# CS_EPS.net
KiCad netlist of a schematic drawn in EAGLE
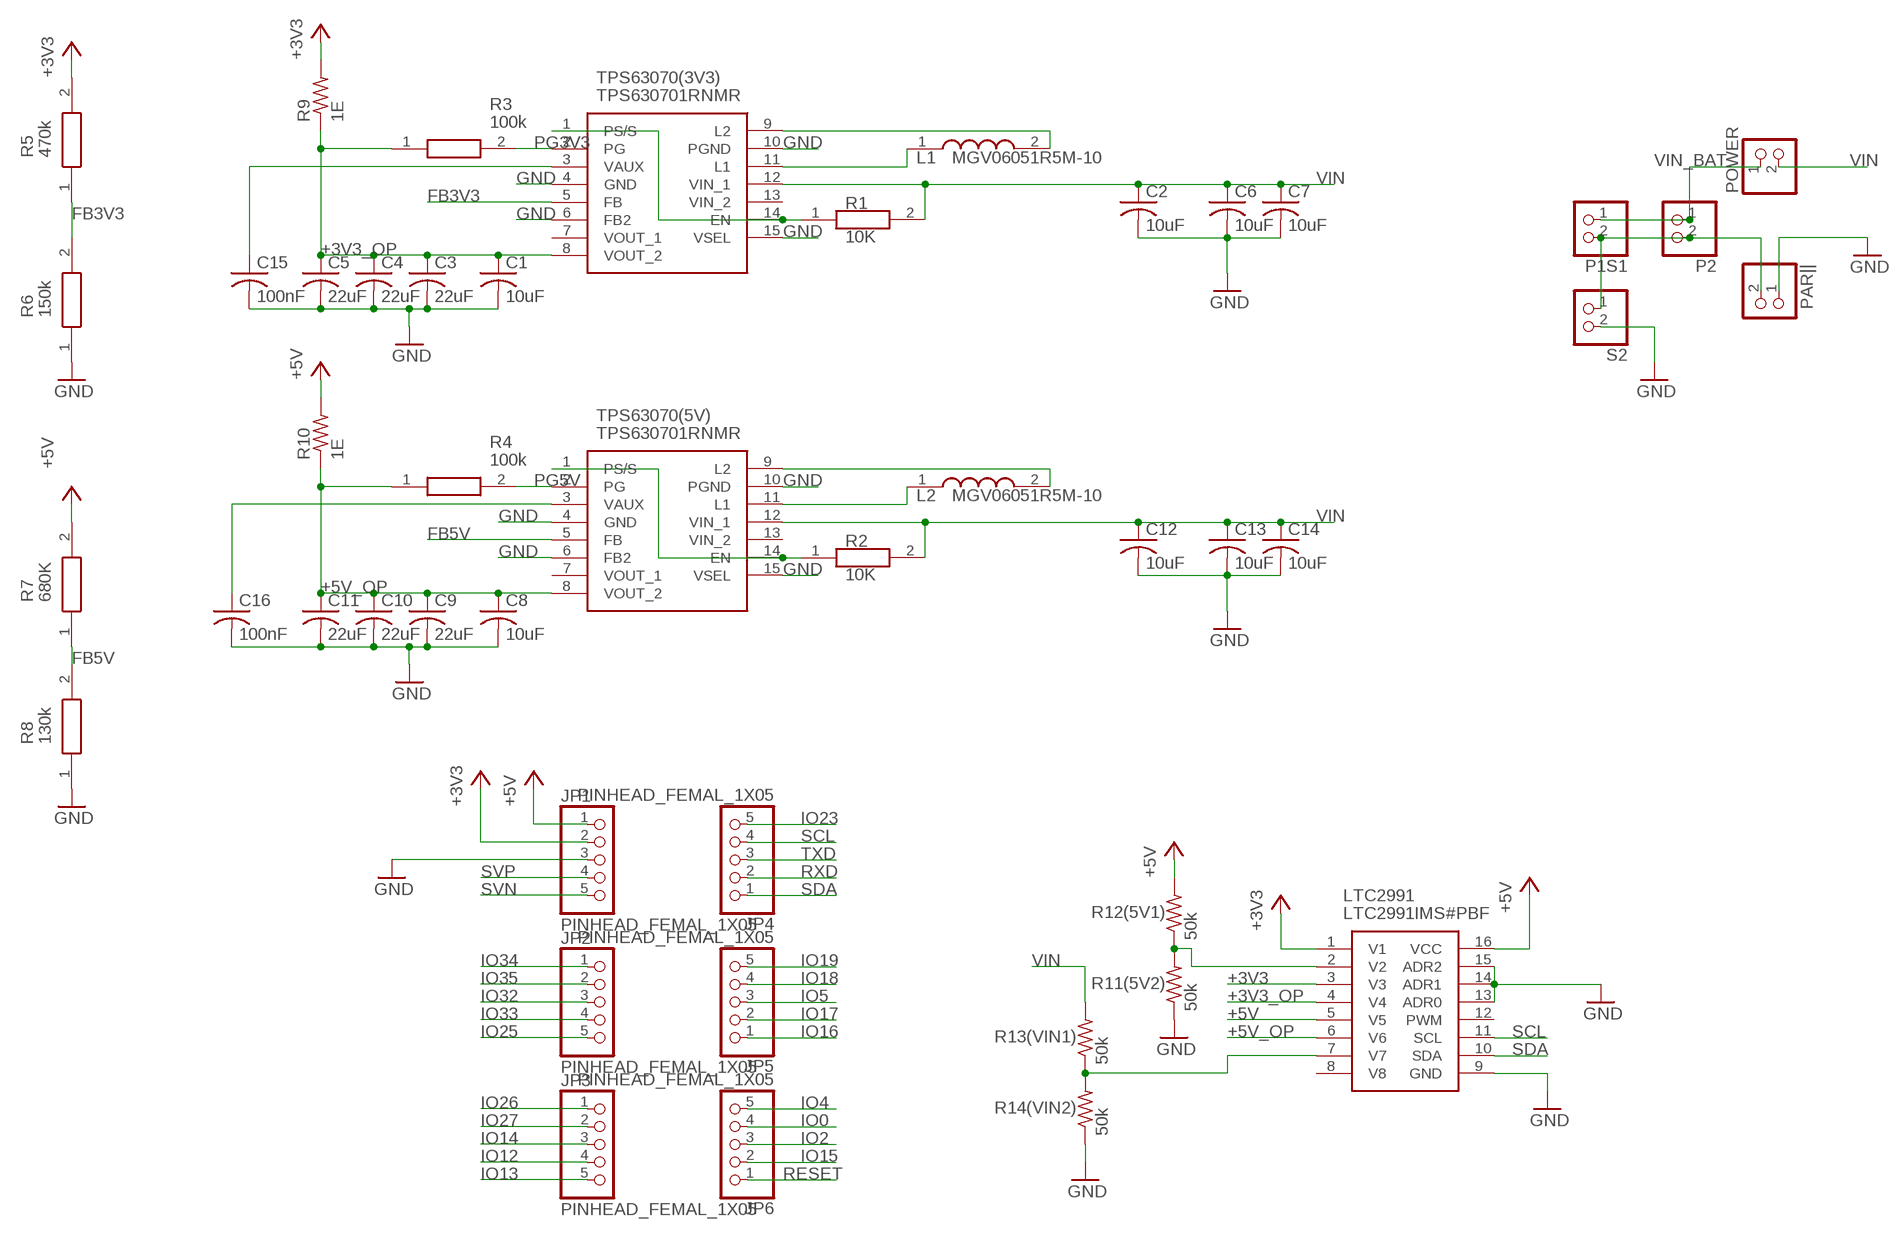
[diagram p0: schematic, sheet 1]

(export (version "E")
  (design (tool "Eeschema 10.0.6"))
  (components
    (comp (ref "C1")
      (value "10uF")
      (footprint "eagle-import:C0603K")
      (libsource (lib "eagle-import") (part "C-USC0603K"))
    )
    (comp (ref "C2")
      (value "10uF")
      (footprint "eagle-import:C0603K")
      (libsource (lib "eagle-import") (part "C-USC0603K"))
    )
    (comp (ref "C3")
      (value "22uF")
      (footprint "eagle-import:C0805K")
      (libsource (lib "eagle-import") (part "C-USC0805K"))
    )
    (comp (ref "C4")
      (value "22uF")
      (footprint "eagle-import:C0805K")
      (libsource (lib "eagle-import") (part "C-USC0805K"))
    )
    (comp (ref "C5")
      (value "22uF")
      (footprint "eagle-import:C0805K")
      (libsource (lib "eagle-import") (part "C-USC0805K"))
    )
    (comp (ref "C6")
      (value "10uF")
      (footprint "eagle-import:C0805K")
      (libsource (lib "eagle-import") (part "C-USC0805K"))
    )
    (comp (ref "C7")
      (value "10uF")
      (footprint "eagle-import:C0805K")
      (libsource (lib "eagle-import") (part "C-USC0805K"))
    )
    (comp (ref "C8")
      (value "10uF")
      (footprint "eagle-import:C0603K")
      (libsource (lib "eagle-import") (part "C-USC0603K"))
    )
    (comp (ref "C9")
      (value "22uF")
      (footprint "eagle-import:C0805K")
      (libsource (lib "eagle-import") (part "C-USC0805K"))
    )
    (comp (ref "C10")
      (value "22uF")
      (footprint "eagle-import:C0805K")
      (libsource (lib "eagle-import") (part "C-USC0805K"))
    )
    (comp (ref "C11")
      (value "22uF")
      (footprint "eagle-import:C0805K")
      (libsource (lib "eagle-import") (part "C-USC0805K"))
    )
    (comp (ref "C12")
      (value "10uF")
      (footprint "eagle-import:C0603K")
      (libsource (lib "eagle-import") (part "C-USC0603K"))
    )
    (comp (ref "C13")
      (value "10uF")
      (footprint "eagle-import:C0805K")
      (libsource (lib "eagle-import") (part "C-USC0805K"))
    )
    (comp (ref "C14")
      (value "10uF")
      (footprint "eagle-import:C0805K")
      (libsource (lib "eagle-import") (part "C-USC0805K"))
    )
    (comp (ref "C15")
      (value "100nF")
      (footprint "eagle-import:C0402")
      (libsource (lib "eagle-import") (part "C-USC0402"))
    )
    (comp (ref "C16")
      (value "100nF")
      (footprint "eagle-import:C0402")
      (libsource (lib "eagle-import") (part "C-USC0402"))
    )
    (comp (ref "JP1")
      (value "PINHEAD_FEMAL_1X05")
      (footprint "eagle-import:1X05F")
      (libsource (lib "eagle-import") (part "PINHEAD_FEMAL_1X05"))
    )
    (comp (ref "JP2")
      (value "PINHEAD_FEMAL_1X05")
      (footprint "eagle-import:1X05F")
      (libsource (lib "eagle-import") (part "PINHEAD_FEMAL_1X05"))
    )
    (comp (ref "JP3")
      (value "PINHEAD_FEMAL_1X05")
      (footprint "eagle-import:1X05F")
      (libsource (lib "eagle-import") (part "PINHEAD_FEMAL_1X05"))
    )
    (comp (ref "JP4")
      (value "PINHEAD_FEMAL_1X05")
      (footprint "eagle-import:1X05F")
      (libsource (lib "eagle-import") (part "PINHEAD_FEMAL_1X05"))
    )
    (comp (ref "JP5")
      (value "PINHEAD_FEMAL_1X05")
      (footprint "eagle-import:1X05F")
      (libsource (lib "eagle-import") (part "PINHEAD_FEMAL_1X05"))
    )
    (comp (ref "JP6")
      (value "PINHEAD_FEMAL_1X05")
      (footprint "eagle-import:1X05F")
      (libsource (lib "eagle-import") (part "PINHEAD_FEMAL_1X05"))
    )
    (comp (ref "L1")
      (value "MGV06051R5M-10")
      (footprint "eagle-import:INDPM7367X530N")
      (fields (field (name "MOUSER_PART_NUMBER") "875-MGV06051R5M-10"))
      (libsource (lib "eagle-import") (part "MGV06051R5M-10"))
    )
    (comp (ref "L2")
      (value "MGV06051R5M-10")
      (footprint "eagle-import:INDPM7367X530N")
      (fields (field (name "MOUSER_PART_NUMBER") "875-MGV06051R5M-10"))
      (libsource (lib "eagle-import") (part "MGV06051R5M-10"))
    )
    (comp (ref "LTC2991")
      (value "LTC2991IMS#PBF")
      (footprint "eagle-import:SOP50P490X110-16N")
      (fields (field (name "MOUSER_PART_NUMBER") "584-LTC2991IMS#PBF"))
      (libsource (lib "eagle-import") (part "LTC2991IMS#PBF"))
    )
    (comp (ref "P1S1")
      (value "JST_2PIN-THM")
      (footprint "eagle-import:JST-PH-2-THM")
      (libsource (lib "eagle-import") (part "JST_2PIN-THM"))
    )
    (comp (ref "P2")
      (value "JST_2PIN-THM")
      (footprint "eagle-import:JST-PH-2-THM")
      (libsource (lib "eagle-import") (part "JST_2PIN-THM"))
    )
    (comp (ref "PAR||")
      (value "PINHD-1X2")
      (footprint "eagle-import:1X02")
      (libsource (lib "eagle-import") (part "PINHD-1X2"))
    )
    (comp (ref "POWER")
      (value "PINHD-1X2")
      (footprint "eagle-import:1X02")
      (libsource (lib "eagle-import") (part "PINHD-1X2"))
    )
    (comp (ref "R1")
      (value "10K")
      (footprint "eagle-import:RESC2012X60N")
      (fields
        (field (name "MANUFACTURER_PART_NUMBER") "ERA-6AED134V")
        (field (name "MOUSER_PART_NUMBER") "667-ERA-6AED134V")
      )
      (libsource (lib "eagle-import") (part "ERA-6AED134V"))
    )
    (comp (ref "R2")
      (value "10K")
      (footprint "eagle-import:RESC2012X60N")
      (fields
        (field (name "MANUFACTURER_PART_NUMBER") "ERA-6AED134V")
        (field (name "MOUSER_PART_NUMBER") "667-ERA-6AED134V")
      )
      (libsource (lib "eagle-import") (part "ERA-6AED134V"))
    )
    (comp (ref "R3")
      (value "100k")
      (footprint "eagle-import:RESC2012X60N")
      (fields
        (field (name "MANUFACTURER_PART_NUMBER") "ERA-6AED134V")
        (field (name "MOUSER_PART_NUMBER") "667-ERA-6AED134V")
      )
      (libsource (lib "eagle-import") (part "ERA-6AED134V"))
    )
    (comp (ref "R4")
      (value "100k")
      (footprint "eagle-import:RESC2012X60N")
      (fields
        (field (name "MANUFACTURER_PART_NUMBER") "ERA-6AED134V")
        (field (name "MOUSER_PART_NUMBER") "667-ERA-6AED134V")
      )
      (libsource (lib "eagle-import") (part "ERA-6AED134V"))
    )
    (comp (ref "R5")
      (value "470k")
      (footprint "eagle-import:RESC2012X60N")
      (fields
        (field (name "MANUFACTURER_PART_NUMBER") "ERA-6AED134V")
        (field (name "MOUSER_PART_NUMBER") "667-ERA-6AED134V")
      )
      (libsource (lib "eagle-import") (part "ERA-6AED134V"))
    )
    (comp (ref "R6")
      (value "150k")
      (footprint "eagle-import:RESC2012X60N")
      (fields
        (field (name "MANUFACTURER_PART_NUMBER") "ERA-6AED134V")
        (field (name "MOUSER_PART_NUMBER") "667-ERA-6AED134V")
      )
      (libsource (lib "eagle-import") (part "ERA-6AED134V"))
    )
    (comp (ref "R7")
      (value "680K")
      (footprint "eagle-import:RESC2012X60N")
      (fields
        (field (name "MANUFACTURER_PART_NUMBER") "ERA-6AED134V")
        (field (name "MOUSER_PART_NUMBER") "667-ERA-6AED134V")
      )
      (libsource (lib "eagle-import") (part "ERA-6AED134V"))
    )
    (comp (ref "R8")
      (value "130k")
      (footprint "eagle-import:RESC2012X60N")
      (fields
        (field (name "MANUFACTURER_PART_NUMBER") "ERA-6AED134V")
        (field (name "MOUSER_PART_NUMBER") "667-ERA-6AED134V")
      )
      (libsource (lib "eagle-import") (part "ERA-6AED134V"))
    )
    (comp (ref "R9")
      (value "1E")
      (footprint "eagle-import:R0805")
      (libsource (lib "eagle-import") (part "R-US_R0805"))
    )
    (comp (ref "R10")
      (value "1E")
      (footprint "eagle-import:R0805")
      (libsource (lib "eagle-import") (part "R-US_R0805"))
    )
    (comp (ref "R11(5V2)")
      (value "50k")
      (footprint "eagle-import:R0805")
      (libsource (lib "eagle-import") (part "R-US_R0805"))
    )
    (comp (ref "R12(5V1)")
      (value "50k")
      (footprint "eagle-import:R0805")
      (libsource (lib "eagle-import") (part "R-US_R0805"))
    )
    (comp (ref "R13(VIN1)")
      (value "50k")
      (footprint "eagle-import:R0805")
      (libsource (lib "eagle-import") (part "R-US_R0805"))
    )
    (comp (ref "R14(VIN2)")
      (value "50k")
      (footprint "eagle-import:R0805")
      (libsource (lib "eagle-import") (part "R-US_R0805"))
    )
    (comp (ref "S2")
      (value "JST_2PIN-THM")
      (footprint "eagle-import:JST-PH-2-THM")
      (libsource (lib "eagle-import") (part "JST_2PIN-THM"))
    )
    (comp (ref "TPS63070(3V3)")
      (value "TPS630701RNMR")
      (footprint "eagle-import:TPS630701RNMR")
      (fields (field (name "MOUSER_PART_NUMBER") "595-TPS630701RNMR"))
      (libsource (lib "eagle-import") (part "TPS630701RNMR"))
    )
    (comp (ref "TPS63070(5V)")
      (value "TPS630701RNMR")
      (footprint "eagle-import:TPS630701RNMR")
      (fields (field (name "MOUSER_PART_NUMBER") "595-TPS630701RNMR"))
      (libsource (lib "eagle-import") (part "TPS630701RNMR"))
    )
  )
  (nets
    (net (code "1") (name "+3V3") (class "Default")
      (node (ref "JP1") (pin "2") (pinfunction "2_2") (pintype "passive"))
      (node (ref "LTC2991") (pin "1") (pinfunction "V1_1") (pintype "bidirectional"))
      (node (ref "LTC2991") (pin "3") (pinfunction "V3_3") (pintype "bidirectional"))
      (node (ref "R5") (pin "2") (pinfunction "2_2") (pintype "bidirectional"))
      (node (ref "R9") (pin "2") (pinfunction "2_2") (pintype "passive"))
    )
    (net (code "2") (name "+5V") (class "Default")
      (node (ref "JP1") (pin "1") (pinfunction "1_1") (pintype "passive"))
      (node (ref "LTC2991") (pin "16") (pinfunction "VCC_16") (pintype "bidirectional"))
      (node (ref "LTC2991") (pin "5") (pinfunction "V5_5") (pintype "bidirectional"))
      (node (ref "R10") (pin "2") (pinfunction "2_2") (pintype "passive"))
      (node (ref "R12(5V1)") (pin "2") (pinfunction "2_2") (pintype "passive"))
      (node (ref "R7") (pin "2") (pinfunction "2_2") (pintype "bidirectional"))
    )
    (net (code "3") (name "/+3V3_OP") (class "Default")
      (node (ref "C1") (pin "1") (pinfunction "1_1") (pintype "passive"))
      (node (ref "C3") (pin "1") (pinfunction "1_1") (pintype "passive"))
      (node (ref "C4") (pin "1") (pinfunction "1_1") (pintype "passive"))
      (node (ref "C5") (pin "1") (pinfunction "1_1") (pintype "passive"))
      (node (ref "LTC2991") (pin "4") (pinfunction "V4_4") (pintype "bidirectional"))
      (node (ref "R3") (pin "1") (pinfunction "1_1") (pintype "bidirectional"))
      (node (ref "R9") (pin "1") (pinfunction "1_1") (pintype "passive"))
      (node (ref "TPS63070(3V3)") (pin "8") (pinfunction "VOUT_2_8") (pintype "bidirectional"))
    )
    (net (code "4") (name "/+5V_OP") (class "Default")
      (node (ref "C10") (pin "1") (pinfunction "1_1") (pintype "passive"))
      (node (ref "C11") (pin "1") (pinfunction "1_1") (pintype "passive"))
      (node (ref "C8") (pin "1") (pinfunction "1_1") (pintype "passive"))
      (node (ref "C9") (pin "1") (pinfunction "1_1") (pintype "passive"))
      (node (ref "LTC2991") (pin "6") (pinfunction "V6_6") (pintype "bidirectional"))
      (node (ref "R10") (pin "1") (pinfunction "1_1") (pintype "passive"))
      (node (ref "R4") (pin "1") (pinfunction "1_1") (pintype "bidirectional"))
      (node (ref "TPS63070(5V)") (pin "8") (pinfunction "VOUT_2_8") (pintype "bidirectional"))
    )
    (net (code "5") (name "/FB3V3") (class "Default")
      (node (ref "R5") (pin "1") (pinfunction "1_1") (pintype "bidirectional"))
      (node (ref "R6") (pin "2") (pinfunction "2_2") (pintype "bidirectional"))
      (node (ref "TPS63070(3V3)") (pin "5") (pinfunction "FB_5") (pintype "bidirectional"))
    )
    (net (code "6") (name "/FB5V") (class "Default")
      (node (ref "R7") (pin "1") (pinfunction "1_1") (pintype "bidirectional"))
      (node (ref "R8") (pin "2") (pinfunction "2_2") (pintype "bidirectional"))
      (node (ref "TPS63070(5V)") (pin "5") (pinfunction "FB_5") (pintype "bidirectional"))
    )
    (net (code "7") (name "/IO0") (class "Default")
      (node (ref "JP6") (pin "4") (pinfunction "4_4") (pintype "passive"))
    )
    (net (code "8") (name "/IO2") (class "Default")
      (node (ref "JP6") (pin "3") (pinfunction "3_3") (pintype "passive"))
    )
    (net (code "9") (name "/IO4") (class "Default")
      (node (ref "JP6") (pin "5") (pinfunction "5_5") (pintype "passive"))
    )
    (net (code "10") (name "/IO5") (class "Default")
      (node (ref "JP5") (pin "3") (pinfunction "3_3") (pintype "passive"))
    )
    (net (code "11") (name "/IO12") (class "Default")
      (node (ref "JP3") (pin "4") (pinfunction "4_4") (pintype "passive"))
    )
    (net (code "12") (name "/IO13") (class "Default")
      (node (ref "JP3") (pin "5") (pinfunction "5_5") (pintype "passive"))
    )
    (net (code "13") (name "/IO14") (class "Default")
      (node (ref "JP3") (pin "3") (pinfunction "3_3") (pintype "passive"))
    )
    (net (code "14") (name "/IO15") (class "Default")
      (node (ref "JP6") (pin "2") (pinfunction "2_2") (pintype "passive"))
    )
    (net (code "15") (name "/IO16") (class "Default")
      (node (ref "JP5") (pin "1") (pinfunction "1_1") (pintype "passive"))
    )
    (net (code "16") (name "/IO17") (class "Default")
      (node (ref "JP5") (pin "2") (pinfunction "2_2") (pintype "passive"))
    )
    (net (code "17") (name "/IO18") (class "Default")
      (node (ref "JP5") (pin "4") (pinfunction "4_4") (pintype "passive"))
    )
    (net (code "18") (name "/IO19") (class "Default")
      (node (ref "JP5") (pin "5") (pinfunction "5_5") (pintype "passive"))
    )
    (net (code "19") (name "/IO23") (class "Default")
      (node (ref "JP4") (pin "5") (pinfunction "5_5") (pintype "passive"))
    )
    (net (code "20") (name "/IO25") (class "Default")
      (node (ref "JP2") (pin "5") (pinfunction "5_5") (pintype "passive"))
    )
    (net (code "21") (name "/IO26") (class "Default")
      (node (ref "JP3") (pin "1") (pinfunction "1_1") (pintype "passive"))
    )
    (net (code "22") (name "/IO27") (class "Default")
      (node (ref "JP3") (pin "2") (pinfunction "2_2") (pintype "passive"))
    )
    (net (code "23") (name "/IO32") (class "Default")
      (node (ref "JP2") (pin "3") (pinfunction "3_3") (pintype "passive"))
    )
    (net (code "24") (name "/IO33") (class "Default")
      (node (ref "JP2") (pin "4") (pinfunction "4_4") (pintype "passive"))
    )
    (net (code "25") (name "/IO34") (class "Default")
      (node (ref "JP2") (pin "1") (pinfunction "1_1") (pintype "passive"))
    )
    (net (code "26") (name "/IO35") (class "Default")
      (node (ref "JP2") (pin "2") (pinfunction "2_2") (pintype "passive"))
    )
    (net (code "27") (name "/PG3V3") (class "Default")
      (node (ref "R3") (pin "2") (pinfunction "2_2") (pintype "bidirectional"))
      (node (ref "TPS63070(3V3)") (pin "2") (pinfunction "PG_2") (pintype "bidirectional"))
    )
    (net (code "28") (name "/PG5V") (class "Default")
      (node (ref "R4") (pin "2") (pinfunction "2_2") (pintype "bidirectional"))
      (node (ref "TPS63070(5V)") (pin "2") (pinfunction "PG_2") (pintype "bidirectional"))
    )
    (net (code "29") (name "/RESET") (class "Default")
      (node (ref "JP6") (pin "1") (pinfunction "1_1") (pintype "passive"))
    )
    (net (code "30") (name "/RXD") (class "Default")
      (node (ref "JP4") (pin "2") (pinfunction "2_2") (pintype "passive"))
    )
    (net (code "31") (name "/SCL") (class "Default")
      (node (ref "JP4") (pin "4") (pinfunction "4_4") (pintype "passive"))
      (node (ref "LTC2991") (pin "11") (pinfunction "SCL_11") (pintype "bidirectional"))
    )
    (net (code "32") (name "/SDA") (class "Default")
      (node (ref "JP4") (pin "1") (pinfunction "1_1") (pintype "passive"))
      (node (ref "LTC2991") (pin "10") (pinfunction "SDA_10") (pintype "bidirectional"))
    )
    (net (code "33") (name "/SVN") (class "Default")
      (node (ref "JP1") (pin "5") (pinfunction "5_5") (pintype "passive"))
    )
    (net (code "34") (name "/SVP") (class "Default")
      (node (ref "JP1") (pin "4") (pinfunction "4_4") (pintype "passive"))
    )
    (net (code "35") (name "/TXD") (class "Default")
      (node (ref "JP4") (pin "3") (pinfunction "3_3") (pintype "passive"))
    )
    (net (code "36") (name "/VIN") (class "Default")
      (node (ref "C12") (pin "1") (pinfunction "1_1") (pintype "passive"))
      (node (ref "C13") (pin "1") (pinfunction "1_1") (pintype "passive"))
      (node (ref "C14") (pin "1") (pinfunction "1_1") (pintype "passive"))
      (node (ref "C2") (pin "1") (pinfunction "1_1") (pintype "passive"))
      (node (ref "C6") (pin "1") (pinfunction "1_1") (pintype "passive"))
      (node (ref "C7") (pin "1") (pinfunction "1_1") (pintype "passive"))
      (node (ref "POWER") (pin "2") (pinfunction "2_2") (pintype "passive"))
      (node (ref "R1") (pin "2") (pinfunction "2_2") (pintype "bidirectional"))
      (node (ref "R13(VIN1)") (pin "2") (pinfunction "2_2") (pintype "passive"))
      (node (ref "R2") (pin "2") (pinfunction "2_2") (pintype "bidirectional"))
      (node (ref "TPS63070(3V3)") (pin "12") (pinfunction "VIN_1_12") (pintype "bidirectional"))
      (node (ref "TPS63070(5V)") (pin "12") (pinfunction "VIN_1_12") (pintype "bidirectional"))
    )
    (net (code "37") (name "/VIN_BAT") (class "Default")
      (node (ref "P1S1") (pin "1") (pinfunction "2_1") (pintype "passive"))
      (node (ref "P2") (pin "1") (pinfunction "2_1") (pintype "passive"))
      (node (ref "POWER") (pin "1") (pinfunction "1_1") (pintype "passive"))
    )
    (net (code "38") (name "GND") (class "Default")
      (node (ref "C1") (pin "2") (pinfunction "2_2") (pintype "passive"))
      (node (ref "C10") (pin "2") (pinfunction "2_2") (pintype "passive"))
      (node (ref "C11") (pin "2") (pinfunction "2_2") (pintype "passive"))
      (node (ref "C12") (pin "2") (pinfunction "2_2") (pintype "passive"))
      (node (ref "C13") (pin "2") (pinfunction "2_2") (pintype "passive"))
      (node (ref "C14") (pin "2") (pinfunction "2_2") (pintype "passive"))
      (node (ref "C15") (pin "2") (pinfunction "2_2") (pintype "passive"))
      (node (ref "C16") (pin "2") (pinfunction "2_2") (pintype "passive"))
      (node (ref "C2") (pin "2") (pinfunction "2_2") (pintype "passive"))
      (node (ref "C3") (pin "2") (pinfunction "2_2") (pintype "passive"))
      (node (ref "C4") (pin "2") (pinfunction "2_2") (pintype "passive"))
      (node (ref "C5") (pin "2") (pinfunction "2_2") (pintype "passive"))
      (node (ref "C6") (pin "2") (pinfunction "2_2") (pintype "passive"))
      (node (ref "C7") (pin "2") (pinfunction "2_2") (pintype "passive"))
      (node (ref "C8") (pin "2") (pinfunction "2_2") (pintype "passive"))
      (node (ref "C9") (pin "2") (pinfunction "2_2") (pintype "passive"))
      (node (ref "JP1") (pin "3") (pinfunction "3_3") (pintype "passive"))
      (node (ref "LTC2991") (pin "13") (pinfunction "ADR0_13") (pintype "bidirectional"))
      (node (ref "LTC2991") (pin "14") (pinfunction "ADR1_14") (pintype "bidirectional"))
      (node (ref "LTC2991") (pin "15") (pinfunction "ADR2_15") (pintype "bidirectional"))
      (node (ref "LTC2991") (pin "9") (pinfunction "GND_9") (pintype "bidirectional"))
      (node (ref "PAR||") (pin "1") (pinfunction "1_1") (pintype "passive"))
      (node (ref "R11(5V2)") (pin "1") (pinfunction "1_1") (pintype "passive"))
      (node (ref "R14(VIN2)") (pin "1") (pinfunction "1_1") (pintype "passive"))
      (node (ref "R6") (pin "1") (pinfunction "1_1") (pintype "bidirectional"))
      (node (ref "R8") (pin "1") (pinfunction "1_1") (pintype "bidirectional"))
      (node (ref "S2") (pin "2") (pinfunction "1_2") (pintype "passive"))
      (node (ref "TPS63070(3V3)") (pin "10") (pinfunction "PGND_10") (pintype "bidirectional"))
      (node (ref "TPS63070(3V3)") (pin "15") (pinfunction "VSEL_15") (pintype "bidirectional"))
      (node (ref "TPS63070(3V3)") (pin "4") (pinfunction "GND_4") (pintype "bidirectional"))
      (node (ref "TPS63070(3V3)") (pin "6") (pinfunction "FB2_6") (pintype "bidirectional"))
      (node (ref "TPS63070(5V)") (pin "10") (pinfunction "PGND_10") (pintype "bidirectional"))
      (node (ref "TPS63070(5V)") (pin "15") (pinfunction "VSEL_15") (pintype "bidirectional"))
      (node (ref "TPS63070(5V)") (pin "4") (pinfunction "GND_4") (pintype "bidirectional"))
      (node (ref "TPS63070(5V)") (pin "6") (pinfunction "FB2_6") (pintype "bidirectional"))
    )
    (net (code "39") (name "Net-(LTC2991-V2)") (class "Default")
      (node (ref "LTC2991") (pin "2") (pinfunction "V2_2") (pintype "bidirectional"))
      (node (ref "R11(5V2)") (pin "2") (pinfunction "2_2") (pintype "passive"))
      (node (ref "R12(5V1)") (pin "1") (pinfunction "1_1") (pintype "passive"))
    )
    (net (code "40") (name "Net-(LTC2991-V7)") (class "Default")
      (node (ref "LTC2991") (pin "7") (pinfunction "V7_7") (pintype "bidirectional"))
      (node (ref "R13(VIN1)") (pin "1") (pinfunction "1_1") (pintype "passive"))
      (node (ref "R14(VIN2)") (pin "2") (pinfunction "2_2") (pintype "passive"))
    )
    (net (code "41") (name "Net-(P1S1-1)") (class "Default")
      (node (ref "P1S1") (pin "2") (pinfunction "1_2") (pintype "passive"))
      (node (ref "P2") (pin "2") (pinfunction "1_2") (pintype "passive"))
      (node (ref "PAR||") (pin "2") (pinfunction "2_2") (pintype "passive"))
      (node (ref "S2") (pin "1") (pinfunction "2_1") (pintype "passive"))
    )
    (net (code "42") (name "Net-(TPS63070(3V3)-EN)") (class "Default")
      (node (ref "R1") (pin "1") (pinfunction "1_1") (pintype "bidirectional"))
      (node (ref "TPS63070(3V3)") (pin "1") (pinfunction "PS/S_1") (pintype "bidirectional"))
      (node (ref "TPS63070(3V3)") (pin "14") (pinfunction "EN_14") (pintype "bidirectional"))
    )
    (net (code "43") (name "Net-(TPS63070(3V3)-L1)") (class "Default")
      (node (ref "L1") (pin "1") (pinfunction "1_1") (pintype "bidirectional"))
      (node (ref "TPS63070(3V3)") (pin "11") (pinfunction "L1_11") (pintype "bidirectional"))
    )
    (net (code "44") (name "Net-(TPS63070(3V3)-L2)") (class "Default")
      (node (ref "L1") (pin "2") (pinfunction "2_2") (pintype "bidirectional"))
      (node (ref "TPS63070(3V3)") (pin "9") (pinfunction "L2_9") (pintype "bidirectional"))
    )
    (net (code "45") (name "Net-(TPS63070(3V3)-VAUX)") (class "Default")
      (node (ref "C15") (pin "1") (pinfunction "1_1") (pintype "passive"))
      (node (ref "TPS63070(3V3)") (pin "3") (pinfunction "VAUX_3") (pintype "bidirectional"))
    )
    (net (code "46") (name "Net-(TPS63070(5V)-EN)") (class "Default")
      (node (ref "R2") (pin "1") (pinfunction "1_1") (pintype "bidirectional"))
      (node (ref "TPS63070(5V)") (pin "1") (pinfunction "PS/S_1") (pintype "bidirectional"))
      (node (ref "TPS63070(5V)") (pin "14") (pinfunction "EN_14") (pintype "bidirectional"))
    )
    (net (code "47") (name "Net-(TPS63070(5V)-L1)") (class "Default")
      (node (ref "L2") (pin "1") (pinfunction "1_1") (pintype "bidirectional"))
      (node (ref "TPS63070(5V)") (pin "11") (pinfunction "L1_11") (pintype "bidirectional"))
    )
    (net (code "48") (name "Net-(TPS63070(5V)-L2)") (class "Default")
      (node (ref "L2") (pin "2") (pinfunction "2_2") (pintype "bidirectional"))
      (node (ref "TPS63070(5V)") (pin "9") (pinfunction "L2_9") (pintype "bidirectional"))
    )
    (net (code "49") (name "Net-(TPS63070(5V)-VAUX)") (class "Default")
      (node (ref "C16") (pin "1") (pinfunction "1_1") (pintype "passive"))
      (node (ref "TPS63070(5V)") (pin "3") (pinfunction "VAUX_3") (pintype "bidirectional"))
    )
    (net (code "50") (name "unconnected-(LTC2991-PWM-Pad12)") (class "Default")
      (node (ref "LTC2991") (pin "12") (pinfunction "PWM_12") (pintype "bidirectional"))
    )
    (net (code "51") (name "unconnected-(LTC2991-V8-Pad8)") (class "Default")
      (node (ref "LTC2991") (pin "8") (pinfunction "V8_8") (pintype "bidirectional"))
    )
    (net (code "52") (name "unconnected-(TPS63070(3V3)-VIN_2-Pad13)") (class "Default")
      (node (ref "TPS63070(3V3)") (pin "13") (pinfunction "VIN_2_13") (pintype "bidirectional"))
    )
    (net (code "53") (name "unconnected-(TPS63070(3V3)-VOUT_1-Pad7)") (class "Default")
      (node (ref "TPS63070(3V3)") (pin "7") (pinfunction "VOUT_1_7") (pintype "bidirectional"))
    )
    (net (code "54") (name "unconnected-(TPS63070(5V)-VIN_2-Pad13)") (class "Default")
      (node (ref "TPS63070(5V)") (pin "13") (pinfunction "VIN_2_13") (pintype "bidirectional"))
    )
    (net (code "55") (name "unconnected-(TPS63070(5V)-VOUT_1-Pad7)") (class "Default")
      (node (ref "TPS63070(5V)") (pin "7") (pinfunction "VOUT_1_7") (pintype "bidirectional"))
    )
  )
)
